# Power.net
KiCad netlist of a schematic drawn in Altium Designer
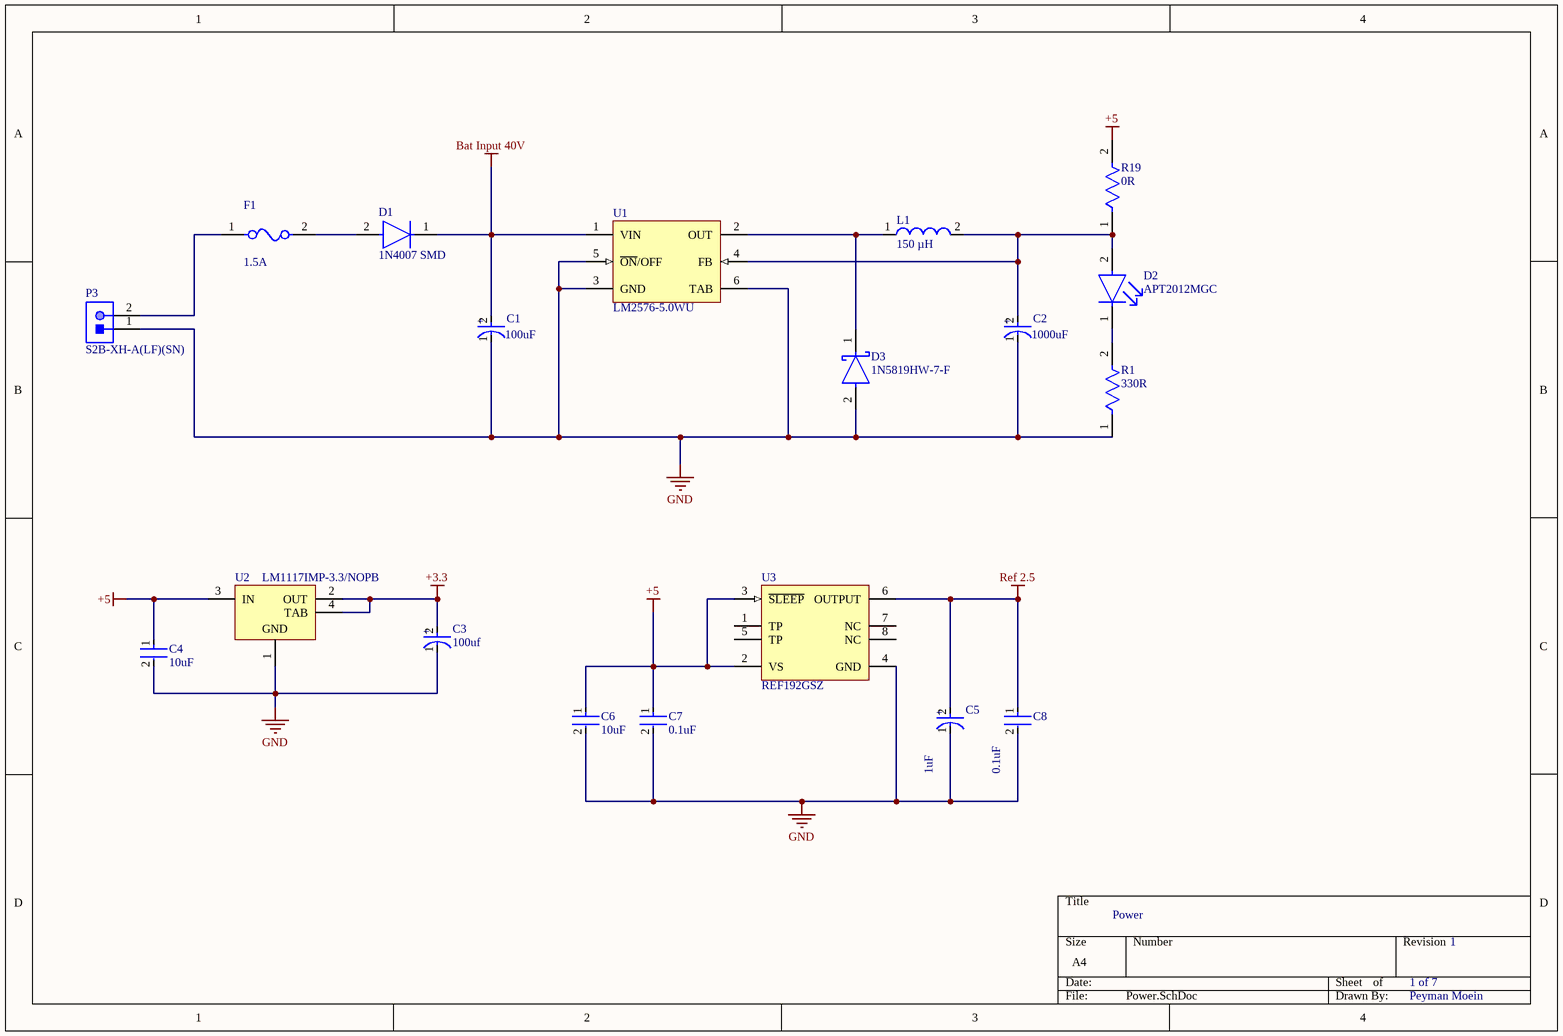
[diagram p0: Power.SchDoc]

(export (version "E")
  (design (tool "Eeschema 10.0.6"))
  (components
    (comp (ref "C1")
      (value "100uF")
      (footprint "FP-UWT1H101MNL1GS-MFG")
      (description "C445063")
      (fields (field (name "TOLERANCE") "20%") (field (name "VOLTAGE") "50V"))
      (libsource (lib "Altium Content Vault") (part "203bc49f2ac43e59fd269a8c329ed05"))
    )
    (comp (ref "C2")
      (value "1000uF")
      (footprint "FP-SVPF-F12-MFG")
      (description "C236289")
      (fields (field (name "VOLTAGE") "16V") (field (name "TOLERANCE") "20%"))
      (libsource (lib "Altium Content Vault") (part "203bc49f2ac43e59fd269a8c329ed05"))
    )
    (comp (ref "C3")
      (value "100uf")
      (footprint "FP-SC-MFG")
      (description "C128464")
      (fields (field (name "VOLTAGE") "35V") (field (name "TOLERANCE") "20%"))
      (libsource (lib "Altium Content Vault") (part "a00bbbee19879c290e62620ae7e47b1"))
    )
    (comp (ref "C4")
      (value "10uF")
      (footprint "FP-GRM21B-0_1-IPC_C")
      (description "C77075")
      (fields (field (name "TOLERANCE") "10%") (field (name "VOLTAGE") "16V"))
      (libsource (lib "Altium Content Vault") (part "b4654b650e69147ec39a6b967a45e02"))
    )
    (comp (ref "C5")
      (value "1uF")
      (footprint "FP-T491A105K016AT-MFG")
      (description "C116269")
      (fields (field (name "TOLERANCE") "20%") (field (name "VOLTAGE") "16V"))
      (libsource (lib "Altium Content Vault") (part "203bc49f2ac43e59fd269a8c329ed05"))
    )
    (comp (ref "C6")
      (value "10uF")
      (footprint "FP-GRM21B-0_1-IPC_C")
      (description "C77075")
      (fields (field (name "TOLERANCE") "10%") (field (name "VOLTAGE") "16V"))
      (libsource (lib "Altium Content Vault") (part "b4654b650e69147ec39a6b967a45e02"))
    )
    (comp (ref "C7")
      (value "0.1uF")
      (footprint "FP-C0805C-DN-MFG")
      (description "C49678")
      (fields (field (name "TOLERANCE") "0.1") (field (name "MANUFACTURER PART NUMBER") "CC0805KRX7R9BB104"))
      (libsource (lib "Altium Content Vault") (part "11868f565c42a9108669ba33697ecf6"))
    )
    (comp (ref "C8")
      (value "0.1uF")
      (footprint "FP-C0805C-DN-MFG")
      (description "C49678")
      (fields (field (name "TOLERANCE") "0.1") (field (name "MANUFACTURER PART NUMBER") "CC0805KRX7R9BB104"))
      (libsource (lib "Altium Content Vault") (part "11868f565c42a9108669ba33697ecf6"))
    )
    (comp (ref "D1")
      (value "1N4007 SMD")
      (footprint "FP-1N4007_SMD-IPC_C")
      (description "C727081")
      (libsource (lib "Altium Content Vault") (part "d7152d700b627762746794eb795d46e"))
    )
    (comp (ref "D2")
      (value "APT2012MGC")
      (footprint "FP-APT2012MGC-MFG")
      (description "C138557")
      (libsource (lib "Altium Content Vault") (part "8706943c75ba83719d021d2fdc84c58"))
    )
    (comp (ref "D3")
      (value "1N5819HW-7-F")
      (footprint "FP-SOD123-IPC_A")
      (description "DIODE SCHOTTKY 40V 1A SOD123")
      (libsource (lib "Altium Content Vault") (part "1d6ec82d83fb6aee721767c19dac4b9"))
    )
    (comp (ref "F1")
      (value "1.5A")
      (footprint "FP-0679H-MFG")
      (description "C178994")
      (fields
        (field (name "MANUFACTURER PART NUMBER") "0448005.MR")
        (field (name "OCTOPART") "https://octopart.com/0448005.mr-littelfuse-672815")
      )
      (libsource (lib "Altium Content Vault") (part "5bcf9b9f640e542cf0359d10258e979"))
    )
    (comp (ref "L1")
      (value "150 µH")
      (footprint "WE-PD-XL")
      (description "C169397")
      (libsource (lib "Altium Content Vault") (part "PAS-IND-INDUCTOR-2"))
    )
    (comp (ref "P3")
      (value "S2B-XH-A(LF)(SN)")
      (footprint "JST-S2B-XH-A(LF)(SN)_V")
      (description "C157931")
      (fields (field (name "TOLERANCE") "10%"))
      (libsource (lib "Altium Content Vault") (part "CN-1P-M-R2"))
    )
    (comp (ref "R1")
      (value "330R")
      (footprint "FP-CRCW0805-e3-MFG")
      (description "C17630")
      (fields (field (name "TOLERANCE") "1%"))
      (libsource (lib "Altium Content Vault") (part "1029c3af85768c4190bb7ad29bc67b5"))
    )
    (comp (ref "R19")
      (value "0R")
      (footprint "FP-CRCW0805-e3-MFG")
      (description "C25275")
      (fields (field (name "TOLERANCE") "1%"))
      (libsource (lib "Altium Content Vault") (part "1029c3af85768c4190bb7ad29bc67b5"))
    )
    (comp (ref "U1")
      (value "LM2576-5.0WU")
      (footprint "FP-TO263-5LD-PL-1-MFG")
      (description "C77782")
      (fields (field (name "MANUFACTURER") "Texas Instruments"))
      (libsource (lib "Altium Content Vault") (part "PM-REG-LM2575HVS-12"))
    )
    (comp (ref "U2")
      (value "LM1117IMP-3.3/NOPB")
      (footprint "DCY0004A_N")
      (description "C129334")
      (fields (field (name "MANUFACTURER") "Texas Instruments"))
      (libsource (lib "Altium Content Vault") (part "PM-REG-LM1086-SOT4"))
    )
    (comp (ref "U3")
      (value "REF192GSZ")
      (footprint "ADI-R-8_M")
      (description "C581299")
      (fields (field (name "MANUFACTURER") "Analog Devices"))
      (libsource (lib "Altium Content Vault") (part "ADI-REF19X-8"))
    )
  )
  (nets
    (net (code "1") (name "+3.3") (class "Default")
      (node (ref "C3") (pin "2") (pinfunction "A_2") (pintype "passive"))
      (node (ref "U2") (pin "2") (pinfunction "OUT_2") (pintype "power_in"))
      (node (ref "U2") (pin "4") (pinfunction "TAB_4") (pintype "power_in"))
    )
    (net (code "2") (name "+5") (class "Default")
      (node (ref "C4") (pin "1") (pinfunction "1_1") (pintype "passive"))
      (node (ref "C6") (pin "1") (pinfunction "1_1") (pintype "passive"))
      (node (ref "C7") (pin "1") (pinfunction "1_1") (pintype "passive"))
      (node (ref "R19") (pin "2") (pinfunction "2_2") (pintype "passive"))
      (node (ref "U2") (pin "3") (pinfunction "IN_3") (pintype "power_in"))
      (node (ref "U3") (pin "2") (pinfunction "VS_2") (pintype "power_in"))
      (node (ref "U3") (pin "3") (pinfunction "~{SLEEP}_3") (pintype "input"))
    )
    (net (code "3") (name "Bat Input 40V") (class "Default")
      (node (ref "C1") (pin "2") (pinfunction "A_2") (pintype "passive"))
      (node (ref "D1") (pin "1") (pinfunction "C_1") (pintype "passive"))
      (node (ref "U1") (pin "1") (pinfunction "VIN_1") (pintype "power_in"))
    )
    (net (code "4") (name "GND") (class "Default")
      (node (ref "C1") (pin "1") (pinfunction "C_1") (pintype "passive"))
      (node (ref "C2") (pin "1") (pinfunction "C_1") (pintype "passive"))
      (node (ref "C3") (pin "1") (pinfunction "C_1") (pintype "passive"))
      (node (ref "C4") (pin "2") (pinfunction "2_2") (pintype "passive"))
      (node (ref "C5") (pin "1") (pinfunction "C_1") (pintype "passive"))
      (node (ref "C6") (pin "2") (pinfunction "2_2") (pintype "passive"))
      (node (ref "C7") (pin "2") (pinfunction "2_2") (pintype "passive"))
      (node (ref "C8") (pin "2") (pinfunction "2_2") (pintype "passive"))
      (node (ref "D3") (pin "2") (pinfunction "A_2") (pintype "passive"))
      (node (ref "P3") (pin "1") (pinfunction "1_1") (pintype "passive"))
      (node (ref "R1") (pin "1") (pinfunction "1_1") (pintype "passive"))
      (node (ref "U1") (pin "3") (pinfunction "GND_3") (pintype "power_in"))
      (node (ref "U1") (pin "5") (pinfunction "~{ON}/OFF_5") (pintype "input"))
      (node (ref "U1") (pin "6") (pinfunction "TAB_6") (pintype "power_in"))
      (node (ref "U2") (pin "1") (pinfunction "GND_1") (pintype "power_in"))
      (node (ref "U3") (pin "4") (pinfunction "GND_4") (pintype "power_in"))
    )
    (net (code "5") (name "Net-(C2-A)") (class "Default")
      (node (ref "C2") (pin "2") (pinfunction "A_2") (pintype "passive"))
      (node (ref "D2") (pin "2") (pinfunction "A_2") (pintype "passive"))
      (node (ref "L1") (pin "2") (pinfunction "2_2") (pintype "passive"))
      (node (ref "R19") (pin "1") (pinfunction "1_1") (pintype "passive"))
      (node (ref "U1") (pin "4") (pinfunction "FB_4") (pintype "input"))
    )
    (net (code "6") (name "Net-(D1-A)") (class "Default")
      (node (ref "D1") (pin "2") (pinfunction "A_2") (pintype "passive"))
      (node (ref "F1") (pin "2") (pinfunction "2_2") (pintype "passive"))
    )
    (net (code "7") (name "Net-(D2-C)") (class "Default")
      (node (ref "D2") (pin "1") (pinfunction "C_1") (pintype "passive"))
      (node (ref "R1") (pin "2") (pinfunction "2_2") (pintype "passive"))
    )
    (net (code "8") (name "Net-(D3-C)") (class "Default")
      (node (ref "D3") (pin "1") (pinfunction "C_1") (pintype "passive"))
      (node (ref "L1") (pin "1") (pinfunction "1_1") (pintype "passive"))
      (node (ref "U1") (pin "2") (pinfunction "OUT_2") (pintype "power_in"))
    )
    (net (code "9") (name "Net-(F1-Pad1)") (class "Default")
      (node (ref "F1") (pin "1") (pinfunction "1_1") (pintype "passive"))
      (node (ref "P3") (pin "2") (pinfunction "2_2") (pintype "passive"))
    )
    (net (code "10") (name "Ref 2.5") (class "Default")
      (node (ref "C5") (pin "2") (pinfunction "A_2") (pintype "passive"))
      (node (ref "C8") (pin "1") (pinfunction "1_1") (pintype "passive"))
      (node (ref "U3") (pin "6") (pinfunction "OUTPUT_6") (pintype "tri_state"))
    )
    (net (code "11") (name "unconnected-(U3-NC-Pad7)") (class "Default")
      (node (ref "U3") (pin "7") (pinfunction "NC_7") (pintype "passive"))
    )
    (net (code "12") (name "unconnected-(U3-NC-Pad8)") (class "Default")
      (node (ref "U3") (pin "8") (pinfunction "NC_8") (pintype "passive"))
    )
    (net (code "13") (name "unconnected-(U3-TP-Pad1)") (class "Default")
      (node (ref "U3") (pin "1") (pinfunction "TP_1") (pintype "passive"))
    )
    (net (code "14") (name "unconnected-(U3-TP-Pad5)") (class "Default")
      (node (ref "U3") (pin "5") (pinfunction "TP_5") (pintype "passive"))
    )
  )
)
